# DB4100_MCU_v0_2.net
KiCad netlist of a schematic drawn in Altium Designer
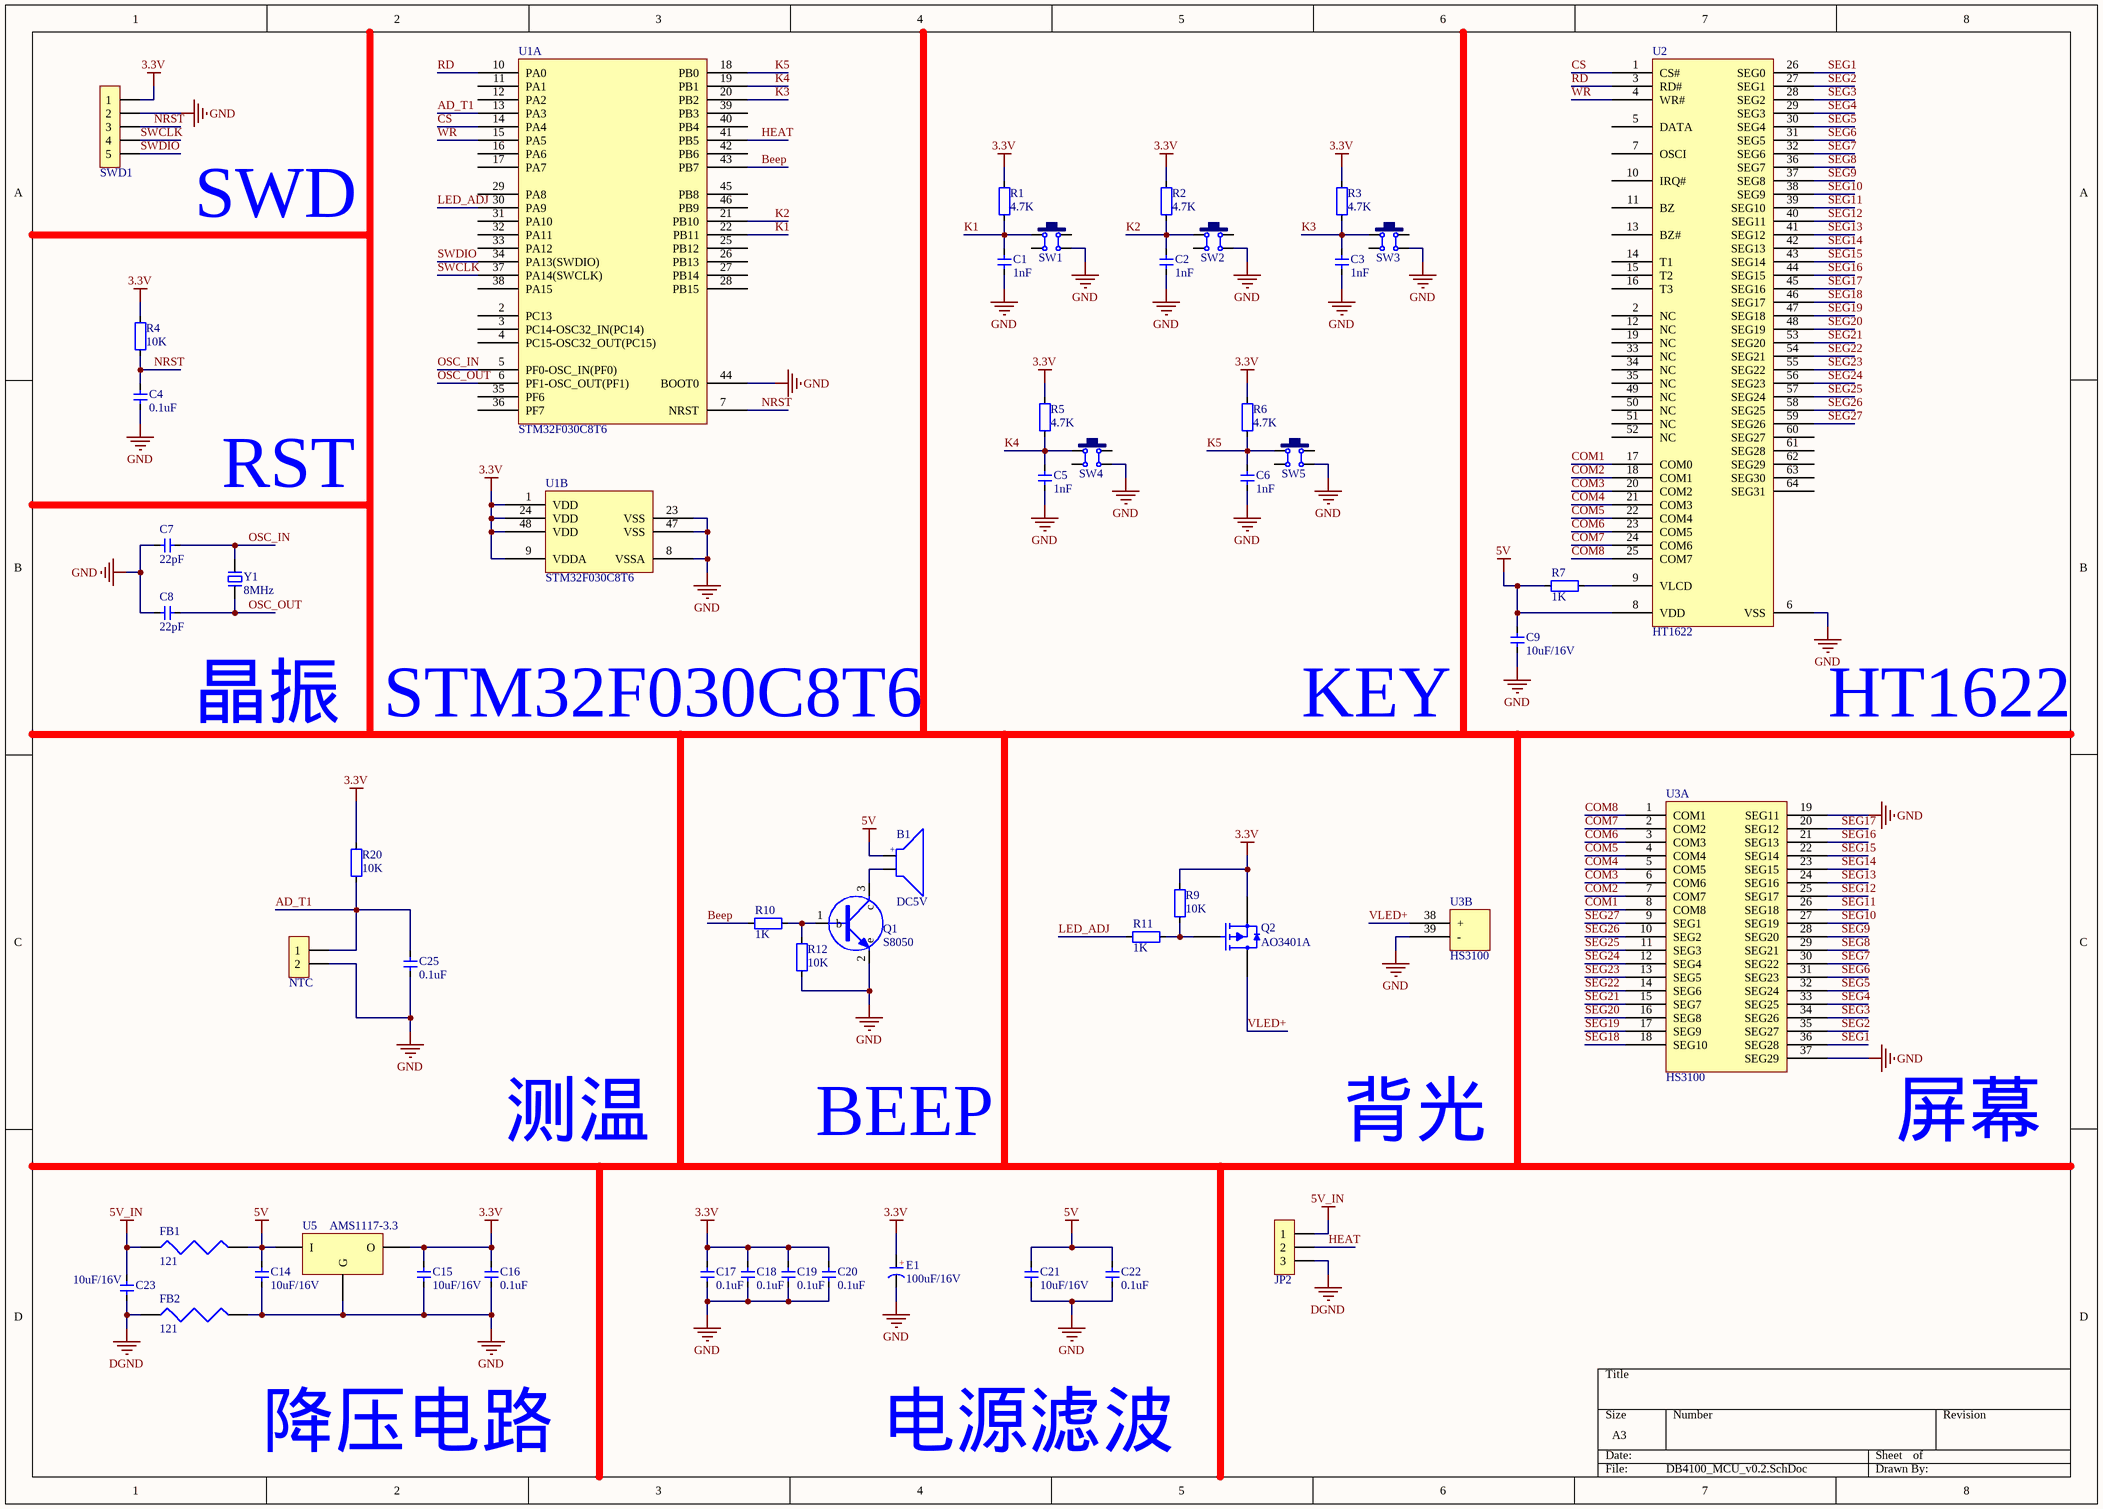
[diagram p0: DB4100_MCU_v0.2.SchDoc]

(export (version "E")
  (design (tool "Eeschema 10.0.6"))
  (components
    (comp (ref "B1")
      (value "DC5V")
      (footprint "BEEP 7.6X12X7.5")
      (description "蜂鸣器")
      (fields (field (name "版权归属") "源创客"))
      (libsource (lib "模块器件") (part "BEEP"))
    )
    (comp (ref "C1")
      (value "1nF")
      (footprint "C 0603")
      (description "无极性贴片电容")
      (fields (field (name "版权归属") "源创客"))
      (libsource (lib "电容") (part "C"))
    )
    (comp (ref "C2")
      (value "1nF")
      (footprint "C 0603")
      (description "无极性贴片电容")
      (fields (field (name "版权归属") "源创客"))
      (libsource (lib "电容") (part "C"))
    )
    (comp (ref "C3")
      (value "1nF")
      (footprint "C 0603")
      (description "无极性贴片电容")
      (fields (field (name "版权归属") "源创客"))
      (libsource (lib "电容") (part "C"))
    )
    (comp (ref "C4")
      (value "0.1uF")
      (footprint "C 0603")
      (description "无极性贴片电容")
      (fields (field (name "版权归属") "源创客"))
      (libsource (lib "电容") (part "C"))
    )
    (comp (ref "C5")
      (value "1nF")
      (footprint "C 0603")
      (description "无极性贴片电容")
      (fields (field (name "版权归属") "源创客"))
      (libsource (lib "电容") (part "C"))
    )
    (comp (ref "C6")
      (value "1nF")
      (footprint "C 0603")
      (description "无极性贴片电容")
      (fields (field (name "版权归属") "源创客"))
      (libsource (lib "电容") (part "C"))
    )
    (comp (ref "C7")
      (value "22pF")
      (footprint "C 0603")
      (description "无极性贴片电容")
      (fields (field (name "版权归属") "源创客"))
      (libsource (lib "电容") (part "C"))
    )
    (comp (ref "C8")
      (value "22pF")
      (footprint "C 0603")
      (description "无极性贴片电容")
      (fields (field (name "版权归属") "源创客"))
      (libsource (lib "电容") (part "C"))
    )
    (comp (ref "C9")
      (value "10uF/16V")
      (footprint "C 0805")
      (description "无极性贴片电容")
      (fields (field (name "版权归属") "源创客"))
      (libsource (lib "电容") (part "C"))
    )
    (comp (ref "C14")
      (value "10uF/16V")
      (footprint "C 0805")
      (description "无极性贴片电容")
      (fields (field (name "版权归属") "源创客"))
      (libsource (lib "电容") (part "C"))
    )
    (comp (ref "C15")
      (value "10uF/16V")
      (footprint "C 0805")
      (description "无极性贴片电容")
      (fields (field (name "版权归属") "源创客"))
      (libsource (lib "电容") (part "C"))
    )
    (comp (ref "C16")
      (value "0.1uF")
      (footprint "C 0603")
      (description "无极性贴片电容")
      (fields (field (name "版权归属") "源创客"))
      (libsource (lib "电容") (part "C"))
    )
    (comp (ref "C17")
      (value "0.1uF")
      (footprint "C 0603")
      (description "无极性贴片电容")
      (fields (field (name "版权归属") "源创客"))
      (libsource (lib "电容") (part "C"))
    )
    (comp (ref "C18")
      (value "0.1uF")
      (footprint "C 0603")
      (description "无极性贴片电容")
      (fields (field (name "版权归属") "源创客"))
      (libsource (lib "电容") (part "C"))
    )
    (comp (ref "C19")
      (value "0.1uF")
      (footprint "C 0603")
      (description "无极性贴片电容")
      (fields (field (name "版权归属") "源创客"))
      (libsource (lib "电容") (part "C"))
    )
    (comp (ref "C20")
      (value "0.1uF")
      (footprint "C 0603")
      (description "无极性贴片电容")
      (fields (field (name "版权归属") "源创客"))
      (libsource (lib "电容") (part "C"))
    )
    (comp (ref "C21")
      (value "10uF/16V")
      (footprint "C 0805")
      (description "无极性贴片电容")
      (fields (field (name "版权归属") "源创客"))
      (libsource (lib "电容") (part "C"))
    )
    (comp (ref "C22")
      (value "0.1uF")
      (footprint "C 0603")
      (description "无极性贴片电容")
      (fields (field (name "版权归属") "源创客"))
      (libsource (lib "电容") (part "C"))
    )
    (comp (ref "C23")
      (value "10uF/16V")
      (footprint "C 0805")
      (description "无极性贴片电容")
      (fields (field (name "版权归属") "源创客"))
      (libsource (lib "电容") (part "C"))
    )
    (comp (ref "C25")
      (value "0.1uF")
      (footprint "C 0603")
      (description "无极性贴片电容")
      (fields (field (name "版权归属") "源创客"))
      (libsource (lib "电容") (part "C"))
    )
    (comp (ref "E1")
      (value "100uF/16V")
      (footprint "CM D(6.3*5.4)")
      (description "直插电解电容")
      (fields (field (name "版权归属") "源创客"))
      (libsource (lib "电容") (part "C-CAP"))
    )
    (comp (ref "FB1")
      (value "121")
      (footprint "L 0805")
      (description "磁珠")
      (libsource (lib "电感") (part "FB"))
    )
    (comp (ref "FB2")
      (value "121")
      (footprint "L 0805")
      (description "磁珠")
      (libsource (lib "电感") (part "FB"))
    )
    (comp (ref "JP2")
      (value "HDR-1X3")
      (footprint "XH2.54-3P")
      (description "3P接插件")
      (fields (field (name "版权归属") "源创客"))
      (libsource (lib "排针-排母") (part "Header 3"))
    )
    (comp (ref "NTC")
      (value "HDR-1X2")
      (footprint "XH2.54-2P")
      (description "2P接插件")
      (fields (field (name "版权归属") "源创客"))
      (libsource (lib "排针-排母") (part "Header 2"))
    )
    (comp (ref "Q1") (value "S8050") (footprint "SOT23-3L") (libsource (lib "三极管") (part "NPN")))
    (comp (ref "Q2")
      (value "AO3401A")
      (footprint "SOT23-3")
      (description "P-MOS")
      (libsource (lib "三极管") (part "AO3401A"))
    )
    (comp (ref "R1")
      (value "4.7K")
      (footprint "R 0603")
      (description "贴片电阻")
      (fields (field (name "版权归属") "源创客"))
      (libsource (lib "电阻") (part "R"))
    )
    (comp (ref "R2")
      (value "4.7K")
      (footprint "R 0603")
      (description "贴片电阻")
      (fields (field (name "版权归属") "源创客"))
      (libsource (lib "电阻") (part "R"))
    )
    (comp (ref "R3")
      (value "4.7K")
      (footprint "R 0603")
      (description "贴片电阻")
      (fields (field (name "版权归属") "源创客"))
      (libsource (lib "电阻") (part "R"))
    )
    (comp (ref "R4")
      (value "10K")
      (footprint "R 0603")
      (description "贴片电阻")
      (fields (field (name "版权归属") "源创客"))
      (libsource (lib "电阻") (part "R"))
    )
    (comp (ref "R5")
      (value "4.7K")
      (footprint "R 0603")
      (description "贴片电阻")
      (fields (field (name "版权归属") "源创客"))
      (libsource (lib "电阻") (part "R"))
    )
    (comp (ref "R6")
      (value "4.7K")
      (footprint "R 0603")
      (description "贴片电阻")
      (fields (field (name "版权归属") "源创客"))
      (libsource (lib "电阻") (part "R"))
    )
    (comp (ref "R7")
      (value "1K")
      (footprint "R 0603")
      (description "贴片电阻")
      (fields (field (name "版权归属") "源创客"))
      (libsource (lib "") (part "R_1"))
    )
    (comp (ref "R9")
      (value "10K")
      (footprint "R 0603")
      (description "贴片电阻")
      (fields (field (name "版权归属") "源创客"))
      (libsource (lib "电阻") (part "R"))
    )
    (comp (ref "R10")
      (value "1K")
      (footprint "R 0603")
      (description "贴片电阻")
      (fields (field (name "版权归属") "源创客"))
      (libsource (lib "") (part "R_1"))
    )
    (comp (ref "R11")
      (value "1K")
      (footprint "R 0603")
      (description "贴片电阻")
      (fields (field (name "版权归属") "源创客"))
      (libsource (lib "") (part "R_1"))
    )
    (comp (ref "R12")
      (value "10K")
      (footprint "R 0603")
      (description "贴片电阻")
      (fields (field (name "版权归属") "源创客"))
      (libsource (lib "电阻") (part "R"))
    )
    (comp (ref "R20")
      (value "10K")
      (footprint "R 0603")
      (description "贴片电阻")
      (fields (field (name "版权归属") "源创客"))
      (libsource (lib "电阻") (part "R"))
    )
    (comp (ref "SW1")
      (value "6x6x5")
      (footprint "TSW SMD-6*6*7")
      (description "贴片6x6轻触开关")
      (fields (field (name "版权归属") "源创客"))
      (libsource (lib "按键") (part "TSW SMD-6x6"))
    )
    (comp (ref "SW2")
      (value "6x6x5")
      (footprint "TSW SMD-6*6*7")
      (description "贴片6x6轻触开关")
      (fields (field (name "版权归属") "源创客"))
      (libsource (lib "按键") (part "TSW SMD-6x6"))
    )
    (comp (ref "SW3")
      (value "6x6x5")
      (footprint "TSW SMD-6*6*7")
      (description "贴片6x6轻触开关")
      (fields (field (name "版权归属") "源创客"))
      (libsource (lib "按键") (part "TSW SMD-6x6"))
    )
    (comp (ref "SW4")
      (value "6x6x5")
      (footprint "TSW SMD-6*6*7")
      (description "贴片6x6轻触开关")
      (fields (field (name "版权归属") "源创客"))
      (libsource (lib "按键") (part "TSW SMD-6x6"))
    )
    (comp (ref "SW5")
      (value "6x6x5")
      (footprint "TSW SMD-6*6*7")
      (description "贴片6x6轻触开关")
      (fields (field (name "版权归属") "源创客"))
      (libsource (lib "按键") (part "TSW SMD-6x6"))
    )
    (comp (ref "SWD1")
      (value "HDR-1X5")
      (footprint "XH2.54-5P")
      (description "5P接插件")
      (fields (field (name "版权归属") "源创客"))
      (libsource (lib "排针-排母") (part "Header 5"))
    )
    (comp (ref "U1")
      (value "STM32F030C8T6")
      (footprint "STM32F030C8T6")
      (libsource (lib "STM32系列单片机") (part "STM32F030C8T6"))
    )
    (comp (ref "U2")
      (value "HT1622")
      (footprint "HT1622")
      (description "LCD驱动，64引脚")
      (libsource (lib "显示芯片") (part "HT1622"))
    )
    (comp (ref "U3")
      (value "HS3100")
      (footprint "HS3100")
      (description "HS3100的屏幕")
      (libsource (lib "显示屏幕") (part "HS3100"))
    )
    (comp (ref "U5")
      (value "AMS1117-3.3")
      (footprint "AMS1117-3.3")
      (description "转3.3V电压")
      (libsource (lib "变压器") (part "AMS1117-3.3"))
    )
    (comp (ref "Y1")
      (value "8MHz")
      (footprint "XTAL-49S SMD")
      (description "2脚晶振")
      (fields (field (name "版权归属") "源创客"))
      (libsource (lib "晶振") (part "XTAL-2"))
    )
  )
  (nets
    (net (code "1") (name "/AD_T1") (class "Default")
      (node (ref "C25") (pin "1") (pinfunction "1_1") (pintype "passive"))
      (node (ref "NTC") (pin "1") (pinfunction "1_1") (pintype "passive"))
      (node (ref "R20") (pin "1") (pinfunction "1_1") (pintype "passive"))
      (node (ref "U1") (pin "13") (pinfunction "PA3_13") (pintype "passive"))
    )
    (net (code "2") (name "/Beep") (class "Default")
      (node (ref "R10") (pin "1") (pinfunction "1_1") (pintype "passive"))
      (node (ref "U1") (pin "43") (pinfunction "PB7_43") (pintype "passive"))
    )
    (net (code "3") (name "/COM1") (class "Default")
      (node (ref "U2") (pin "17") (pinfunction "COM0_17") (pintype "passive"))
      (node (ref "U3") (pin "8") (pinfunction "COM8_8") (pintype "passive"))
    )
    (net (code "4") (name "/COM2") (class "Default")
      (node (ref "U2") (pin "18") (pinfunction "COM1_18") (pintype "passive"))
      (node (ref "U3") (pin "7") (pinfunction "COM7_7") (pintype "passive"))
    )
    (net (code "5") (name "/COM3") (class "Default")
      (node (ref "U2") (pin "20") (pinfunction "COM2_20") (pintype "passive"))
      (node (ref "U3") (pin "6") (pinfunction "COM6_6") (pintype "passive"))
    )
    (net (code "6") (name "/COM4") (class "Default")
      (node (ref "U2") (pin "21") (pinfunction "COM3_21") (pintype "passive"))
      (node (ref "U3") (pin "5") (pinfunction "COM5_5") (pintype "passive"))
    )
    (net (code "7") (name "/COM5") (class "Default")
      (node (ref "U2") (pin "22") (pinfunction "COM4_22") (pintype "passive"))
      (node (ref "U3") (pin "4") (pinfunction "COM4_4") (pintype "passive"))
    )
    (net (code "8") (name "/COM6") (class "Default")
      (node (ref "U2") (pin "23") (pinfunction "COM5_23") (pintype "passive"))
      (node (ref "U3") (pin "3") (pinfunction "COM3_3") (pintype "passive"))
    )
    (net (code "9") (name "/COM7") (class "Default")
      (node (ref "U2") (pin "24") (pinfunction "COM6_24") (pintype "passive"))
      (node (ref "U3") (pin "2") (pinfunction "COM2_2") (pintype "passive"))
    )
    (net (code "10") (name "/COM8") (class "Default")
      (node (ref "U2") (pin "25") (pinfunction "COM7_25") (pintype "passive"))
      (node (ref "U3") (pin "1") (pinfunction "COM1_1") (pintype "passive"))
    )
    (net (code "11") (name "/CS") (class "Default")
      (node (ref "U1") (pin "14") (pinfunction "PA4_14") (pintype "passive"))
      (node (ref "U2") (pin "1") (pinfunction "CS#_1") (pintype "passive"))
    )
    (net (code "12") (name "/HEAT") (class "Default")
      (node (ref "JP2") (pin "2") (pinfunction "2_2") (pintype "passive"))
      (node (ref "U1") (pin "41") (pinfunction "PB5_41") (pintype "passive"))
    )
    (net (code "13") (name "/K1") (class "Default")
      (node (ref "C1") (pin "2") (pinfunction "2_2") (pintype "passive"))
      (node (ref "R1") (pin "1") (pinfunction "1_1") (pintype "passive"))
      (node (ref "SW1") (pin "1") (pinfunction "1_1") (pintype "passive"))
      (node (ref "U1") (pin "22") (pinfunction "PB11_22") (pintype "passive"))
    )
    (net (code "14") (name "/K2") (class "Default")
      (node (ref "C2") (pin "2") (pinfunction "2_2") (pintype "passive"))
      (node (ref "R2") (pin "1") (pinfunction "1_1") (pintype "passive"))
      (node (ref "SW2") (pin "1") (pinfunction "1_1") (pintype "passive"))
      (node (ref "U1") (pin "21") (pinfunction "PB10_21") (pintype "passive"))
    )
    (net (code "15") (name "/K3") (class "Default")
      (node (ref "C3") (pin "2") (pinfunction "2_2") (pintype "passive"))
      (node (ref "R3") (pin "1") (pinfunction "1_1") (pintype "passive"))
      (node (ref "SW3") (pin "1") (pinfunction "1_1") (pintype "passive"))
      (node (ref "U1") (pin "20") (pinfunction "PB2_20") (pintype "passive"))
    )
    (net (code "16") (name "/K4") (class "Default")
      (node (ref "C5") (pin "2") (pinfunction "2_2") (pintype "passive"))
      (node (ref "R5") (pin "1") (pinfunction "1_1") (pintype "passive"))
      (node (ref "SW4") (pin "1") (pinfunction "1_1") (pintype "passive"))
      (node (ref "U1") (pin "19") (pinfunction "PB1_19") (pintype "passive"))
    )
    (net (code "17") (name "/K5") (class "Default")
      (node (ref "C6") (pin "2") (pinfunction "2_2") (pintype "passive"))
      (node (ref "R6") (pin "1") (pinfunction "1_1") (pintype "passive"))
      (node (ref "SW5") (pin "1") (pinfunction "1_1") (pintype "passive"))
      (node (ref "U1") (pin "18") (pinfunction "PB0_18") (pintype "passive"))
    )
    (net (code "18") (name "/LED_ADJ") (class "Default")
      (node (ref "R11") (pin "1") (pinfunction "1_1") (pintype "passive"))
      (node (ref "U1") (pin "30") (pinfunction "PA9_30") (pintype "passive"))
    )
    (net (code "19") (name "/NRST") (class "Default")
      (node (ref "C4") (pin "2") (pinfunction "2_2") (pintype "passive"))
      (node (ref "R4") (pin "1") (pinfunction "1_1") (pintype "passive"))
      (node (ref "SWD1") (pin "3") (pinfunction "3_3") (pintype "passive"))
      (node (ref "U1") (pin "7") (pinfunction "NRST_7") (pintype "passive"))
    )
    (net (code "20") (name "/OSC_IN") (class "Default")
      (node (ref "C7") (pin "2") (pinfunction "2_2") (pintype "passive"))
      (node (ref "U1") (pin "5") (pinfunction "PF0-OSC_IN(PF0)_5") (pintype "passive"))
      (node (ref "Y1") (pin "2") (pinfunction "2_2") (pintype "passive"))
    )
    (net (code "21") (name "/OSC_OUT") (class "Default")
      (node (ref "C8") (pin "2") (pinfunction "2_2") (pintype "passive"))
      (node (ref "U1") (pin "6") (pinfunction "PF1-OSC_OUT(PF1)_6") (pintype "passive"))
      (node (ref "Y1") (pin "1") (pinfunction "1_1") (pintype "passive"))
    )
    (net (code "22") (name "/RD") (class "Default")
      (node (ref "U1") (pin "10") (pinfunction "PA0_10") (pintype "passive"))
      (node (ref "U2") (pin "3") (pinfunction "RD#_3") (pintype "passive"))
    )
    (net (code "23") (name "/SEG1") (class "Default")
      (node (ref "U2") (pin "26") (pinfunction "SEG0_26") (pintype "passive"))
      (node (ref "U3") (pin "36") (pinfunction "SEG28_36") (pintype "passive"))
    )
    (net (code "24") (name "/SEG2") (class "Default")
      (node (ref "U2") (pin "27") (pinfunction "SEG1_27") (pintype "passive"))
      (node (ref "U3") (pin "35") (pinfunction "SEG27_35") (pintype "passive"))
    )
    (net (code "25") (name "/SEG3") (class "Default")
      (node (ref "U2") (pin "28") (pinfunction "SEG2_28") (pintype "passive"))
      (node (ref "U3") (pin "34") (pinfunction "SEG26_34") (pintype "passive"))
    )
    (net (code "26") (name "/SEG4") (class "Default")
      (node (ref "U2") (pin "29") (pinfunction "SEG3_29") (pintype "passive"))
      (node (ref "U3") (pin "33") (pinfunction "SEG25_33") (pintype "passive"))
    )
    (net (code "27") (name "/SEG5") (class "Default")
      (node (ref "U2") (pin "30") (pinfunction "SEG4_30") (pintype "passive"))
      (node (ref "U3") (pin "32") (pinfunction "SEG24_32") (pintype "passive"))
    )
    (net (code "28") (name "/SEG6") (class "Default")
      (node (ref "U2") (pin "31") (pinfunction "SEG5_31") (pintype "passive"))
      (node (ref "U3") (pin "31") (pinfunction "SEG23_31") (pintype "passive"))
    )
    (net (code "29") (name "/SEG7") (class "Default")
      (node (ref "U2") (pin "32") (pinfunction "SEG6_32") (pintype "passive"))
      (node (ref "U3") (pin "30") (pinfunction "SEG22_30") (pintype "passive"))
    )
    (net (code "30") (name "/SEG8") (class "Default")
      (node (ref "U2") (pin "36") (pinfunction "SEG7_36") (pintype "passive"))
      (node (ref "U3") (pin "29") (pinfunction "SEG21_29") (pintype "passive"))
    )
    (net (code "31") (name "/SEG9") (class "Default")
      (node (ref "U2") (pin "37") (pinfunction "SEG8_37") (pintype "passive"))
      (node (ref "U3") (pin "28") (pinfunction "SEG20_28") (pintype "passive"))
    )
    (net (code "32") (name "/SEG10") (class "Default")
      (node (ref "U2") (pin "38") (pinfunction "SEG9_38") (pintype "passive"))
      (node (ref "U3") (pin "27") (pinfunction "SEG19_27") (pintype "passive"))
    )
    (net (code "33") (name "/SEG11") (class "Default")
      (node (ref "U2") (pin "39") (pinfunction "SEG10_39") (pintype "passive"))
      (node (ref "U3") (pin "26") (pinfunction "SEG18_26") (pintype "passive"))
    )
    (net (code "34") (name "/SEG12") (class "Default")
      (node (ref "U2") (pin "40") (pinfunction "SEG11_40") (pintype "passive"))
      (node (ref "U3") (pin "25") (pinfunction "SEG17_25") (pintype "passive"))
    )
    (net (code "35") (name "/SEG13") (class "Default")
      (node (ref "U2") (pin "41") (pinfunction "SEG12_41") (pintype "passive"))
      (node (ref "U3") (pin "24") (pinfunction "SEG16_24") (pintype "passive"))
    )
    (net (code "36") (name "/SEG14") (class "Default")
      (node (ref "U2") (pin "42") (pinfunction "SEG13_42") (pintype "passive"))
      (node (ref "U3") (pin "23") (pinfunction "SEG15_23") (pintype "passive"))
    )
    (net (code "37") (name "/SEG15") (class "Default")
      (node (ref "U2") (pin "43") (pinfunction "SEG14_43") (pintype "passive"))
      (node (ref "U3") (pin "22") (pinfunction "SEG14_22") (pintype "passive"))
    )
    (net (code "38") (name "/SEG16") (class "Default")
      (node (ref "U2") (pin "44") (pinfunction "SEG15_44") (pintype "passive"))
      (node (ref "U3") (pin "21") (pinfunction "SEG13_21") (pintype "passive"))
    )
    (net (code "39") (name "/SEG17") (class "Default")
      (node (ref "U2") (pin "45") (pinfunction "SEG16_45") (pintype "passive"))
      (node (ref "U3") (pin "20") (pinfunction "SEG12_20") (pintype "passive"))
    )
    (net (code "40") (name "/SEG18") (class "Default")
      (node (ref "U2") (pin "46") (pinfunction "SEG17_46") (pintype "passive"))
      (node (ref "U3") (pin "18") (pinfunction "SEG10_18") (pintype "passive"))
    )
    (net (code "41") (name "/SEG19") (class "Default")
      (node (ref "U2") (pin "47") (pinfunction "SEG18_47") (pintype "passive"))
      (node (ref "U3") (pin "17") (pinfunction "SEG9_17") (pintype "passive"))
    )
    (net (code "42") (name "/SEG20") (class "Default")
      (node (ref "U2") (pin "48") (pinfunction "SEG19_48") (pintype "passive"))
      (node (ref "U3") (pin "16") (pinfunction "SEG8_16") (pintype "passive"))
    )
    (net (code "43") (name "/SEG21") (class "Default")
      (node (ref "U2") (pin "53") (pinfunction "SEG20_53") (pintype "passive"))
      (node (ref "U3") (pin "15") (pinfunction "SEG7_15") (pintype "passive"))
    )
    (net (code "44") (name "/SEG22") (class "Default")
      (node (ref "U2") (pin "54") (pinfunction "SEG21_54") (pintype "passive"))
      (node (ref "U3") (pin "14") (pinfunction "SEG6_14") (pintype "passive"))
    )
    (net (code "45") (name "/SEG23") (class "Default")
      (node (ref "U2") (pin "55") (pinfunction "SEG22_55") (pintype "passive"))
      (node (ref "U3") (pin "13") (pinfunction "SEG5_13") (pintype "passive"))
    )
    (net (code "46") (name "/SEG24") (class "Default")
      (node (ref "U2") (pin "56") (pinfunction "SEG23_56") (pintype "passive"))
      (node (ref "U3") (pin "12") (pinfunction "SEG4_12") (pintype "passive"))
    )
    (net (code "47") (name "/SEG25") (class "Default")
      (node (ref "U2") (pin "57") (pinfunction "SEG24_57") (pintype "passive"))
      (node (ref "U3") (pin "11") (pinfunction "SEG3_11") (pintype "passive"))
    )
    (net (code "48") (name "/SEG26") (class "Default")
      (node (ref "U2") (pin "58") (pinfunction "SEG25_58") (pintype "passive"))
      (node (ref "U3") (pin "10") (pinfunction "SEG2_10") (pintype "passive"))
    )
    (net (code "49") (name "/SEG27") (class "Default")
      (node (ref "U2") (pin "59") (pinfunction "SEG26_59") (pintype "passive"))
      (node (ref "U3") (pin "9") (pinfunction "SEG1_9") (pintype "passive"))
    )
    (net (code "50") (name "/SWCLK") (class "Default")
      (node (ref "SWD1") (pin "4") (pinfunction "4_4") (pintype "passive"))
      (node (ref "U1") (pin "37") (pinfunction "PA14(SWCLK)_37") (pintype "passive"))
    )
    (net (code "51") (name "/SWDIO") (class "Default")
      (node (ref "SWD1") (pin "5") (pinfunction "5_5") (pintype "passive"))
      (node (ref "U1") (pin "34") (pinfunction "PA13(SWDIO)_34") (pintype "passive"))
    )
    (net (code "52") (name "/VLED+") (class "Default")
      (node (ref "Q2") (pin "3") (pinfunction "D_3") (pintype "passive"))
      (node (ref "U3") (pin "38") (pinfunction "+_38") (pintype "passive"))
    )
    (net (code "53") (name "/WR") (class "Default")
      (node (ref "U1") (pin "15") (pinfunction "PA5_15") (pintype "passive"))
      (node (ref "U2") (pin "4") (pinfunction "WR#_4") (pintype "passive"))
    )
    (net (code "54") (name "3.3V") (class "Default")
      (node (ref "C15") (pin "2") (pinfunction "2_2") (pintype "passive"))
      (node (ref "C16") (pin "2") (pinfunction "2_2") (pintype "passive"))
      (node (ref "C17") (pin "2") (pinfunction "2_2") (pintype "passive"))
      (node (ref "C18") (pin "2") (pinfunction "2_2") (pintype "passive"))
      (node (ref "C19") (pin "2") (pinfunction "2_2") (pintype "passive"))
      (node (ref "C20") (pin "2") (pinfunction "2_2") (pintype "passive"))
      (node (ref "E1") (pin "1") (pinfunction "A_1") (pintype "passive"))
      (node (ref "Q2") (pin "2") (pinfunction "S_2") (pintype "passive"))
      (node (ref "R1") (pin "2") (pinfunction "2_2") (pintype "passive"))
      (node (ref "R2") (pin "2") (pinfunction "2_2") (pintype "passive"))
      (node (ref "R20") (pin "2") (pinfunction "2_2") (pintype "passive"))
      (node (ref "R3") (pin "2") (pinfunction "2_2") (pintype "passive"))
      (node (ref "R4") (pin "2") (pinfunction "2_2") (pintype "passive"))
      (node (ref "R5") (pin "2") (pinfunction "2_2") (pintype "passive"))
      (node (ref "R6") (pin "2") (pinfunction "2_2") (pintype "passive"))
      (node (ref "R9") (pin "2") (pinfunction "2_2") (pintype "passive"))
      (node (ref "SWD1") (pin "1") (pinfunction "1_1") (pintype "passive"))
      (node (ref "U1") (pin "1") (pinfunction "VDD_1") (pintype "passive"))
      (node (ref "U1") (pin "24") (pinfunction "VDD_24") (pintype "passive"))
      (node (ref "U1") (pin "48") (pinfunction "VDD_48") (pintype "passive"))
      (node (ref "U1") (pin "9") (pinfunction "VDDA_9") (pintype "passive"))
      (node (ref "U5") (pin "2") (pinfunction "O_2") (pintype "passive"))
    )
    (net (code "55") (name "5V") (class "Default")
      (node (ref "B1") (pin "1") (pinfunction "1_1") (pintype "passive"))
      (node (ref "C14") (pin "2") (pinfunction "2_2") (pintype "passive"))
      (node (ref "C21") (pin "2") (pinfunction "2_2") (pintype "passive"))
      (node (ref "C22") (pin "2") (pinfunction "2_2") (pintype "passive"))
      (node (ref "C9") (pin "2") (pinfunction "2_2") (pintype "passive"))
      (node (ref "FB1") (pin "2") (pinfunction "2_2") (pintype "passive"))
      (node (ref "R7") (pin "1") (pinfunction "1_1") (pintype "passive"))
      (node (ref "U2") (pin "8") (pinfunction "VDD_8") (pintype "passive"))
      (node (ref "U5") (pin "3") (pinfunction "I_3") (pintype "passive"))
    )
    (net (code "56") (name "5V_IN") (class "Default")
      (node (ref "C23") (pin "2") (pinfunction "2_2") (pintype "passive"))
      (node (ref "FB1") (pin "1") (pinfunction "1_1") (pintype "passive"))
      (node (ref "JP2") (pin "1") (pinfunction "1_1") (pintype "passive"))
    )
    (net (code "57") (name "DGND") (class "Default")
      (node (ref "C23") (pin "1") (pinfunction "1_1") (pintype "passive"))
      (node (ref "FB2") (pin "1") (pinfunction "1_1") (pintype "passive"))
      (node (ref "JP2") (pin "3") (pinfunction "3_3") (pintype "passive"))
    )
    (net (code "58") (name "GND") (class "Default")
      (node (ref "C1") (pin "1") (pinfunction "1_1") (pintype "passive"))
      (node (ref "C14") (pin "1") (pinfunction "1_1") (pintype "passive"))
      (node (ref "C15") (pin "1") (pinfunction "1_1") (pintype "passive"))
      (node (ref "C16") (pin "1") (pinfunction "1_1") (pintype "passive"))
      (node (ref "C17") (pin "1") (pinfunction "1_1") (pintype "passive"))
      (node (ref "C18") (pin "1") (pinfunction "1_1") (pintype "passive"))
      (node (ref "C19") (pin "1") (pinfunction "1_1") (pintype "passive"))
      (node (ref "C2") (pin "1") (pinfunction "1_1") (pintype "passive"))
      (node (ref "C20") (pin "1") (pinfunction "1_1") (pintype "passive"))
      (node (ref "C21") (pin "1") (pinfunction "1_1") (pintype "passive"))
      (node (ref "C22") (pin "1") (pinfunction "1_1") (pintype "passive"))
      (node (ref "C25") (pin "2") (pinfunction "2_2") (pintype "passive"))
      (node (ref "C3") (pin "1") (pinfunction "1_1") (pintype "passive"))
      (node (ref "C4") (pin "1") (pinfunction "1_1") (pintype "passive"))
      (node (ref "C5") (pin "1") (pinfunction "1_1") (pintype "passive"))
      (node (ref "C6") (pin "1") (pinfunction "1_1") (pintype "passive"))
      (node (ref "C7") (pin "1") (pinfunction "1_1") (pintype "passive"))
      (node (ref "C8") (pin "1") (pinfunction "1_1") (pintype "passive"))
      (node (ref "C9") (pin "1") (pinfunction "1_1") (pintype "passive"))
      (node (ref "E1") (pin "2") (pinfunction "K_2") (pintype "passive"))
      (node (ref "FB2") (pin "2") (pinfunction "2_2") (pintype "passive"))
      (node (ref "NTC") (pin "2") (pinfunction "2_2") (pintype "passive"))
      (node (ref "Q1") (pin "2") (pinfunction "e_2") (pintype "passive"))
      (node (ref "R12") (pin "1") (pinfunction "1_1") (pintype "passive"))
      (node (ref "SW1") (pin "3") (pinfunction "3_3") (pintype "passive"))
      (node (ref "SW2") (pin "3") (pinfunction "3_3") (pintype "passive"))
      (node (ref "SW3") (pin "3") (pinfunction "3_3") (pintype "passive"))
      (node (ref "SW4") (pin "3") (pinfunction "3_3") (pintype "passive"))
      (node (ref "SW5") (pin "3") (pinfunction "3_3") (pintype "passive"))
      (node (ref "SWD1") (pin "2") (pinfunction "2_2") (pintype "passive"))
      (node (ref "U1") (pin "23") (pinfunction "VSS_23") (pintype "passive"))
      (node (ref "U1") (pin "44") (pinfunction "BOOT0_44") (pintype "passive"))
      (node (ref "U1") (pin "47") (pinfunction "VSS_47") (pintype "passive"))
      (node (ref "U1") (pin "8") (pinfunction "VSSA_8") (pintype "passive"))
      (node (ref "U2") (pin "6") (pinfunction "VSS_6") (pintype "passive"))
      (node (ref "U3") (pin "19") (pinfunction "SEG11_19") (pintype "passive"))
      (node (ref "U3") (pin "37") (pinfunction "SEG29_37") (pintype "passive"))
      (node (ref "U3") (pin "39") (pinfunction "-_39") (pintype "passive"))
      (node (ref "U5") (pin "1") (pinfunction "G_1") (pintype "passive"))
    )
    (net (code "59") (name "Net-(Q1-b)") (class "Default")
      (node (ref "Q1") (pin "1") (pinfunction "b_1") (pintype "passive"))
      (node (ref "R10") (pin "2") (pinfunction "2_2") (pintype "passive"))
      (node (ref "R12") (pin "2") (pinfunction "2_2") (pintype "passive"))
    )
    (net (code "60") (name "Net-(Q1-c)") (class "Default")
      (node (ref "B1") (pin "2") (pinfunction "2_2") (pintype "passive"))
      (node (ref "Q1") (pin "3") (pinfunction "c_3") (pintype "passive"))
    )
    (net (code "61") (name "Net-(Q2-G)") (class "Default")
      (node (ref "Q2") (pin "1") (pinfunction "G_1") (pintype "passive"))
      (node (ref "R11") (pin "2") (pinfunction "2_2") (pintype "passive"))
      (node (ref "R9") (pin "1") (pinfunction "1_1") (pintype "passive"))
    )
    (net (code "62") (name "Net-(U2-VLCD)") (class "Default")
      (node (ref "R7") (pin "2") (pinfunction "2_2") (pintype "passive"))
      (node (ref "U2") (pin "9") (pinfunction "VLCD_9") (pintype "passive"))
    )
    (net (code "63") (name "unconnected-(SW1-Pad2)") (class "Default")
      (node (ref "SW1") (pin "2") (pinfunction "2_2") (pintype "passive"))
    )
    (net (code "64") (name "unconnected-(SW1-Pad4)") (class "Default")
      (node (ref "SW1") (pin "4") (pinfunction "4_4") (pintype "passive"))
    )
    (net (code "65") (name "unconnected-(SW2-Pad2)") (class "Default")
      (node (ref "SW2") (pin "2") (pinfunction "2_2") (pintype "passive"))
    )
    (net (code "66") (name "unconnected-(SW2-Pad4)") (class "Default")
      (node (ref "SW2") (pin "4") (pinfunction "4_4") (pintype "passive"))
    )
    (net (code "67") (name "unconnected-(SW3-Pad2)") (class "Default")
      (node (ref "SW3") (pin "2") (pinfunction "2_2") (pintype "passive"))
    )
    (net (code "68") (name "unconnected-(SW3-Pad4)") (class "Default")
      (node (ref "SW3") (pin "4") (pinfunction "4_4") (pintype "passive"))
    )
    (net (code "69") (name "unconnected-(SW4-Pad2)") (class "Default")
      (node (ref "SW4") (pin "2") (pinfunction "2_2") (pintype "passive"))
    )
    (net (code "70") (name "unconnected-(SW4-Pad4)") (class "Default")
      (node (ref "SW4") (pin "4") (pinfunction "4_4") (pintype "passive"))
    )
    (net (code "71") (name "unconnected-(SW5-Pad2)") (class "Default")
      (node (ref "SW5") (pin "2") (pinfunction "2_2") (pintype "passive"))
    )
    (net (code "72") (name "unconnected-(SW5-Pad4)") (class "Default")
      (node (ref "SW5") (pin "4") (pinfunction "4_4") (pintype "passive"))
    )
    (net (code "73") (name "unconnected-(U1A-PA1-Pad11)") (class "Default")
      (node (ref "U1") (pin "11") (pinfunction "PA1_11") (pintype "passive"))
    )
    (net (code "74") (name "unconnected-(U1A-PA2-Pad12)") (class "Default")
      (node (ref "U1") (pin "12") (pinfunction "PA2_12") (pintype "passive"))
    )
    (net (code "75") (name "unconnected-(U1A-PA6-Pad16)") (class "Default")
      (node (ref "U1") (pin "16") (pinfunction "PA6_16") (pintype "passive"))
    )
    (net (code "76") (name "unconnected-(U1A-PA7-Pad17)") (class "Default")
      (node (ref "U1") (pin "17") (pinfunction "PA7_17") (pintype "passive"))
    )
    (net (code "77") (name "unconnected-(U1A-PA8-Pad29)") (class "Default")
      (node (ref "U1") (pin "29") (pinfunction "PA8_29") (pintype "passive"))
    )
    (net (code "78") (name "unconnected-(U1A-PA10-Pad31)") (class "Default")
      (node (ref "U1") (pin "31") (pinfunction "PA10_31") (pintype "passive"))
    )
    (net (code "79") (name "unconnected-(U1A-PA11-Pad32)") (class "Default")
      (node (ref "U1") (pin "32") (pinfunction "PA11_32") (pintype "passive"))
    )
    (net (code "80") (name "unconnected-(U1A-PA12-Pad33)") (class "Default")
      (node (ref "U1") (pin "33") (pinfunction "PA12_33") (pintype "passive"))
    )
    (net (code "81") (name "unconnected-(U1A-PA15-Pad38)") (class "Default")
      (node (ref "U1") (pin "38") (pinfunction "PA15_38") (pintype "passive"))
    )
    (net (code "82") (name "unconnected-(U1A-PB3-Pad39)") (class "Default")
      (node (ref "U1") (pin "39") (pinfunction "PB3_39") (pintype "passive"))
    )
    (net (code "83") (name "unconnected-(U1A-PB4-Pad40)") (class "Default")
      (node (ref "U1") (pin "40") (pinfunction "PB4_40") (pintype "passive"))
    )
    (net (code "84") (name "unconnected-(U1A-PB6-Pad42)") (class "Default")
      (node (ref "U1") (pin "42") (pinfunction "PB6_42") (pintype "passive"))
    )
    (net (code "85") (name "unconnected-(U1A-PB8-Pad45)") (class "Default")
      (node (ref "U1") (pin "45") (pinfunction "PB8_45") (pintype "passive"))
    )
    (net (code "86") (name "unconnected-(U1A-PB9-Pad46)") (class "Default")
      (node (ref "U1") (pin "46") (pinfunction "PB9_46") (pintype "passive"))
    )
    (net (code "87") (name "unconnected-(U1A-PB12-Pad25)") (class "Default")
      (node (ref "U1") (pin "25") (pinfunction "PB12_25") (pintype "passive"))
    )
    (net (code "88") (name "unconnected-(U1A-PB13-Pad26)") (class "Default")
      (node (ref "U1") (pin "26") (pinfunction "PB13_26") (pintype "passive"))
    )
    (net (code "89") (name "unconnected-(U1A-PB14-Pad27)") (class "Default")
      (node (ref "U1") (pin "27") (pinfunction "PB14_27") (pintype "passive"))
    )
    (net (code "90") (name "unconnected-(U1A-PB15-Pad28)") (class "Default")
      (node (ref "U1") (pin "28") (pinfunction "PB15_28") (pintype "passive"))
    )
    (net (code "91") (name "unconnected-(U1A-PC13-Pad2)") (class "Default")
      (node (ref "U1") (pin "2") (pinfunction "PC13_2") (pintype "passive"))
    )
    (net (code "92") (name "unconnected-(U1A-PC14-OSC32_IN(PC14)-Pad3)") (class "Default")
      (node (ref "U1") (pin "3") (pinfunction "PC14-OSC32_IN(PC14)_3") (pintype "passive"))
    )
    (net (code "93") (name "unconnected-(U1A-PC15-OSC32_OUT(PC15)-Pad4)") (class "Default")
      (node (ref "U1") (pin "4") (pinfunction "PC15-OSC32_OUT(PC15)_4") (pintype "passive"))
    )
    (net (code "94") (name "unconnected-(U1A-PF6-Pad35)") (class "Default")
      (node (ref "U1") (pin "35") (pinfunction "PF6_35") (pintype "passive"))
    )
    (net (code "95") (name "unconnected-(U1A-PF7-Pad36)") (class "Default")
      (node (ref "U1") (pin "36") (pinfunction "PF7_36") (pintype "passive"))
    )
    (net (code "96") (name "unconnected-(U2-BZ#-Pad13)") (class "Default")
      (node (ref "U2") (pin "13") (pinfunction "BZ#_13") (pintype "passive"))
    )
    (net (code "97") (name "unconnected-(U2-BZ-Pad11)") (class "Default")
      (node (ref "U2") (pin "11") (pinfunction "BZ_11") (pintype "passive"))
    )
    (net (code "98") (name "unconnected-(U2-DATA-Pad5)") (class "Default")
      (node (ref "U2") (pin "5") (pinfunction "DATA_5") (pintype "passive"))
    )
    (net (code "99") (name "unconnected-(U2-IRQ#-Pad10)") (class "Default")
      (node (ref "U2") (pin "10") (pinfunction "IRQ#_10") (pintype "passive"))
    )
    (net (code "100") (name "unconnected-(U2-NC-Pad2)") (class "Default")
      (node (ref "U2") (pin "2") (pinfunction "NC_2") (pintype "passive"))
    )
    (net (code "101") (name "unconnected-(U2-NC-Pad12)") (class "Default")
      (node (ref "U2") (pin "12") (pinfunction "NC_12") (pintype "passive"))
    )
    (net (code "102") (name "unconnected-(U2-NC-Pad19)") (class "Default")
      (node (ref "U2") (pin "19") (pinfunction "NC_19") (pintype "passive"))
    )
    (net (code "103") (name "unconnected-(U2-NC-Pad33)") (class "Default")
      (node (ref "U2") (pin "33") (pinfunction "NC_33") (pintype "passive"))
    )
    (net (code "104") (name "unconnected-(U2-NC-Pad34)") (class "Default")
      (node (ref "U2") (pin "34") (pinfunction "NC_34") (pintype "passive"))
    )
    (net (code "105") (name "unconnected-(U2-NC-Pad35)") (class "Default")
      (node (ref "U2") (pin "35") (pinfunction "NC_35") (pintype "passive"))
    )
    (net (code "106") (name "unconnected-(U2-NC-Pad49)") (class "Default")
      (node (ref "U2") (pin "49") (pinfunction "NC_49") (pintype "passive"))
    )
    (net (code "107") (name "unconnected-(U2-NC-Pad50)") (class "Default")
      (node (ref "U2") (pin "50") (pinfunction "NC_50") (pintype "passive"))
    )
    (net (code "108") (name "unconnected-(U2-NC-Pad51)") (class "Default")
      (node (ref "U2") (pin "51") (pinfunction "NC_51") (pintype "passive"))
    )
    (net (code "109") (name "unconnected-(U2-NC-Pad52)") (class "Default")
      (node (ref "U2") (pin "52") (pinfunction "NC_52") (pintype "passive"))
    )
    (net (code "110") (name "unconnected-(U2-OSCI-Pad7)") (class "Default")
      (node (ref "U2") (pin "7") (pinfunction "OSCI_7") (pintype "passive"))
    )
    (net (code "111") (name "unconnected-(U2-SEG27-Pad60)") (class "Default")
      (node (ref "U2") (pin "60") (pinfunction "SEG27_60") (pintype "passive"))
    )
    (net (code "112") (name "unconnected-(U2-SEG28-Pad61)") (class "Default")
      (node (ref "U2") (pin "61") (pinfunction "SEG28_61") (pintype "passive"))
    )
    (net (code "113") (name "unconnected-(U2-SEG29-Pad62)") (class "Default")
      (node (ref "U2") (pin "62") (pinfunction "SEG29_62") (pintype "passive"))
    )
    (net (code "114") (name "unconnected-(U2-SEG30-Pad63)") (class "Default")
      (node (ref "U2") (pin "63") (pinfunction "SEG30_63") (pintype "passive"))
    )
    (net (code "115") (name "unconnected-(U2-SEG31-Pad64)") (class "Default")
      (node (ref "U2") (pin "64") (pinfunction "SEG31_64") (pintype "passive"))
    )
    (net (code "116") (name "unconnected-(U2-T1-Pad14)") (class "Default")
      (node (ref "U2") (pin "14") (pinfunction "T1_14") (pintype "passive"))
    )
    (net (code "117") (name "unconnected-(U2-T2-Pad15)") (class "Default")
      (node (ref "U2") (pin "15") (pinfunction "T2_15") (pintype "passive"))
    )
    (net (code "118") (name "unconnected-(U2-T3-Pad16)") (class "Default")
      (node (ref "U2") (pin "16") (pinfunction "T3_16") (pintype "passive"))
    )
  )
)
